# phychip_plugin_board.net
KiCad netlist of a schematic drawn in EAGLE
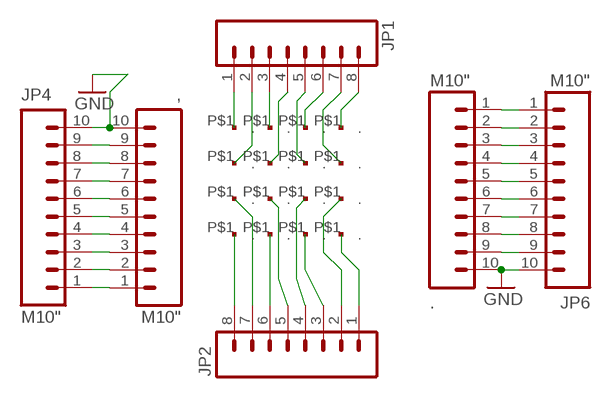
[diagram p0: schematic, sheet 1]

(export (version "E")
  (design (tool "Eeschema 10.0.6"))
  (components
    (comp (ref ",")
      (value "M10\"")
      (footprint "eagle-import:1X10")
      (libsource (lib "eagle-import") (part "M10{dblquote}"))
    )
    (comp (ref ".")
      (value "M10\"")
      (footprint "eagle-import:1X10")
      (libsource (lib "eagle-import") (part "M10{dblquote}"))
    )
    (comp (ref "JP1")
      (value "M08")
      (footprint "eagle-import:1X08")
      (libsource (lib "eagle-import") (part "M08"))
    )
    (comp (ref "JP2")
      (value "M08")
      (footprint "eagle-import:1X08")
      (libsource (lib "eagle-import") (part "M08"))
    )
    (comp (ref "JP4")
      (value "M10\"")
      (footprint "eagle-import:1X10")
      (libsource (lib "eagle-import") (part "M10{dblquote}"))
    )
    (comp (ref "JP6")
      (value "M10\"")
      (footprint "eagle-import:1X10")
      (libsource (lib "eagle-import") (part "M10{dblquote}"))
    )
    (comp (ref "U$1")
      (value "MEAPAD")
      (footprint "eagle-import:MEAPAD1MM")
      (libsource (lib "eagle-import") (part "MEAPAD"))
    )
    (comp (ref "U$2")
      (value "MEAPAD")
      (footprint "eagle-import:MEAPAD1MM")
      (libsource (lib "eagle-import") (part "MEAPAD"))
    )
    (comp (ref "U$3")
      (value "MEAPAD")
      (footprint "eagle-import:MEAPAD1MM")
      (libsource (lib "eagle-import") (part "MEAPAD"))
    )
    (comp (ref "U$4")
      (value "MEAPAD")
      (footprint "eagle-import:MEAPAD1MM")
      (libsource (lib "eagle-import") (part "MEAPAD"))
    )
    (comp (ref "U$5")
      (value "MEAPAD")
      (footprint "eagle-import:MEAPAD1MM")
      (libsource (lib "eagle-import") (part "MEAPAD"))
    )
    (comp (ref "U$6")
      (value "MEAPAD")
      (footprint "eagle-import:MEAPAD1MM")
      (libsource (lib "eagle-import") (part "MEAPAD"))
    )
    (comp (ref "U$7")
      (value "MEAPAD")
      (footprint "eagle-import:MEAPAD1MM")
      (libsource (lib "eagle-import") (part "MEAPAD"))
    )
    (comp (ref "U$8")
      (value "MEAPAD")
      (footprint "eagle-import:MEAPAD1MM")
      (libsource (lib "eagle-import") (part "MEAPAD"))
    )
    (comp (ref "U$9")
      (value "MEAPAD")
      (footprint "eagle-import:MEAPAD1MM")
      (libsource (lib "eagle-import") (part "MEAPAD"))
    )
    (comp (ref "U$10")
      (value "MEAPAD")
      (footprint "eagle-import:MEAPAD1MM")
      (libsource (lib "eagle-import") (part "MEAPAD"))
    )
    (comp (ref "U$11")
      (value "MEAPAD")
      (footprint "eagle-import:MEAPAD1MM")
      (libsource (lib "eagle-import") (part "MEAPAD"))
    )
    (comp (ref "U$12")
      (value "MEAPAD")
      (footprint "eagle-import:MEAPAD1MM")
      (libsource (lib "eagle-import") (part "MEAPAD"))
    )
    (comp (ref "U$13")
      (value "MEAPAD")
      (footprint "eagle-import:MEAPAD1MM")
      (libsource (lib "eagle-import") (part "MEAPAD"))
    )
    (comp (ref "U$14")
      (value "MEAPAD")
      (footprint "eagle-import:MEAPAD1MM")
      (libsource (lib "eagle-import") (part "MEAPAD"))
    )
    (comp (ref "U$15")
      (value "MEAPAD")
      (footprint "eagle-import:MEAPAD1MM")
      (libsource (lib "eagle-import") (part "MEAPAD"))
    )
    (comp (ref "U$16")
      (value "MEAPAD")
      (footprint "eagle-import:MEAPAD1MM")
      (libsource (lib "eagle-import") (part "MEAPAD"))
    )
  )
  (nets
    (net (code "1") (name "GND") (class "Default")
      (node (ref ",") (pin "10") (pinfunction "10_10") (pintype "passive"))
      (node (ref ".") (pin "10") (pinfunction "10_10") (pintype "passive"))
      (node (ref "JP4") (pin "10") (pinfunction "10_10") (pintype "passive"))
      (node (ref "JP6") (pin "10") (pinfunction "10_10") (pintype "passive"))
    )
    (net (code "2") (name "Net-(,-Pad1)") (class "Default")
      (node (ref ",") (pin "1") (pinfunction "1_1") (pintype "passive"))
      (node (ref "JP4") (pin "1") (pinfunction "1_1") (pintype "passive"))
    )
    (net (code "3") (name "Net-(,-Pad2)") (class "Default")
      (node (ref ",") (pin "2") (pinfunction "2_2") (pintype "passive"))
      (node (ref "JP4") (pin "2") (pinfunction "2_2") (pintype "passive"))
    )
    (net (code "4") (name "Net-(,-Pad3)") (class "Default")
      (node (ref ",") (pin "3") (pinfunction "3_3") (pintype "passive"))
      (node (ref "JP4") (pin "3") (pinfunction "3_3") (pintype "passive"))
    )
    (net (code "5") (name "Net-(,-Pad4)") (class "Default")
      (node (ref ",") (pin "4") (pinfunction "4_4") (pintype "passive"))
      (node (ref "JP4") (pin "4") (pinfunction "4_4") (pintype "passive"))
    )
    (net (code "6") (name "Net-(,-Pad5)") (class "Default")
      (node (ref ",") (pin "5") (pinfunction "5_5") (pintype "passive"))
      (node (ref "JP4") (pin "5") (pinfunction "5_5") (pintype "passive"))
    )
    (net (code "7") (name "Net-(,-Pad6)") (class "Default")
      (node (ref ",") (pin "6") (pinfunction "6_6") (pintype "passive"))
      (node (ref "JP4") (pin "6") (pinfunction "6_6") (pintype "passive"))
    )
    (net (code "8") (name "Net-(,-Pad7)") (class "Default")
      (node (ref ",") (pin "7") (pinfunction "7_7") (pintype "passive"))
      (node (ref "JP4") (pin "7") (pinfunction "7_7") (pintype "passive"))
    )
    (net (code "9") (name "Net-(,-Pad8)") (class "Default")
      (node (ref ",") (pin "8") (pinfunction "8_8") (pintype "passive"))
      (node (ref "JP4") (pin "8") (pinfunction "8_8") (pintype "passive"))
    )
    (net (code "10") (name "Net-(,-Pad9)") (class "Default")
      (node (ref ",") (pin "9") (pinfunction "9_9") (pintype "passive"))
      (node (ref "JP4") (pin "9") (pinfunction "9_9") (pintype "passive"))
    )
    (net (code "11") (name "Net-(.-Pad1)") (class "Default")
      (node (ref ".") (pin "1") (pinfunction "1_1") (pintype "passive"))
      (node (ref "JP6") (pin "1") (pinfunction "1_1") (pintype "passive"))
    )
    (net (code "12") (name "Net-(.-Pad2)") (class "Default")
      (node (ref ".") (pin "2") (pinfunction "2_2") (pintype "passive"))
      (node (ref "JP6") (pin "2") (pinfunction "2_2") (pintype "passive"))
    )
    (net (code "13") (name "Net-(.-Pad3)") (class "Default")
      (node (ref ".") (pin "3") (pinfunction "3_3") (pintype "passive"))
      (node (ref "JP6") (pin "3") (pinfunction "3_3") (pintype "passive"))
    )
    (net (code "14") (name "Net-(.-Pad4)") (class "Default")
      (node (ref ".") (pin "4") (pinfunction "4_4") (pintype "passive"))
      (node (ref "JP6") (pin "4") (pinfunction "4_4") (pintype "passive"))
    )
    (net (code "15") (name "Net-(.-Pad5)") (class "Default")
      (node (ref ".") (pin "5") (pinfunction "5_5") (pintype "passive"))
      (node (ref "JP6") (pin "5") (pinfunction "5_5") (pintype "passive"))
    )
    (net (code "16") (name "Net-(.-Pad6)") (class "Default")
      (node (ref ".") (pin "6") (pinfunction "6_6") (pintype "passive"))
      (node (ref "JP6") (pin "6") (pinfunction "6_6") (pintype "passive"))
    )
    (net (code "17") (name "Net-(.-Pad7)") (class "Default")
      (node (ref ".") (pin "7") (pinfunction "7_7") (pintype "passive"))
      (node (ref "JP6") (pin "7") (pinfunction "7_7") (pintype "passive"))
    )
    (net (code "18") (name "Net-(.-Pad8)") (class "Default")
      (node (ref ".") (pin "8") (pinfunction "8_8") (pintype "passive"))
      (node (ref "JP6") (pin "8") (pinfunction "8_8") (pintype "passive"))
    )
    (net (code "19") (name "Net-(.-Pad9)") (class "Default")
      (node (ref ".") (pin "9") (pinfunction "9_9") (pintype "passive"))
      (node (ref "JP6") (pin "9") (pinfunction "9_9") (pintype "passive"))
    )
    (net (code "20") (name "Net-(U$1-.)") (class "Default")
      (node (ref "JP1") (pin "1") (pinfunction "1_1") (pintype "passive"))
      (node (ref "U$1") (pin "P$1") (pinfunction "._P$1") (pintype "bidirectional"))
    )
    (net (code "21") (name "Net-(U$2-.)") (class "Default")
      (node (ref "JP1") (pin "3") (pinfunction "3_3") (pintype "passive"))
      (node (ref "U$2") (pin "P$1") (pinfunction "._P$1") (pintype "bidirectional"))
    )
    (net (code "22") (name "Net-(U$3-.)") (class "Default")
      (node (ref "JP1") (pin "6") (pinfunction "6_6") (pintype "passive"))
      (node (ref "U$3") (pin "P$1") (pinfunction "._P$1") (pintype "bidirectional"))
    )
    (net (code "23") (name "Net-(U$4-.)") (class "Default")
      (node (ref "JP1") (pin "8") (pinfunction "8_8") (pintype "passive"))
      (node (ref "U$4") (pin "P$1") (pinfunction "._P$1") (pintype "bidirectional"))
    )
    (net (code "24") (name "Net-(U$5-.)") (class "Default")
      (node (ref "JP1") (pin "2") (pinfunction "2_2") (pintype "passive"))
      (node (ref "U$5") (pin "P$1") (pinfunction "._P$1") (pintype "bidirectional"))
    )
    (net (code "25") (name "Net-(U$6-.)") (class "Default")
      (node (ref "JP1") (pin "4") (pinfunction "4_4") (pintype "passive"))
      (node (ref "U$6") (pin "P$1") (pinfunction "._P$1") (pintype "bidirectional"))
    )
    (net (code "26") (name "Net-(U$7-.)") (class "Default")
      (node (ref "JP1") (pin "5") (pinfunction "5_5") (pintype "passive"))
      (node (ref "U$7") (pin "P$1") (pinfunction "._P$1") (pintype "bidirectional"))
    )
    (net (code "27") (name "Net-(U$8-.)") (class "Default")
      (node (ref "JP1") (pin "7") (pinfunction "7_7") (pintype "passive"))
      (node (ref "U$8") (pin "P$1") (pinfunction "._P$1") (pintype "bidirectional"))
    )
    (net (code "28") (name "Net-(U$9-.)") (class "Default")
      (node (ref "JP2") (pin "7") (pinfunction "7_7") (pintype "passive"))
      (node (ref "U$9") (pin "P$1") (pinfunction "._P$1") (pintype "bidirectional"))
    )
    (net (code "29") (name "Net-(U$10-.)") (class "Default")
      (node (ref "JP2") (pin "5") (pinfunction "5_5") (pintype "passive"))
      (node (ref "U$10") (pin "P$1") (pinfunction "._P$1") (pintype "bidirectional"))
    )
    (net (code "30") (name "Net-(U$11-.)") (class "Default")
      (node (ref "JP2") (pin "4") (pinfunction "4_4") (pintype "passive"))
      (node (ref "U$11") (pin "P$1") (pinfunction "._P$1") (pintype "bidirectional"))
    )
    (net (code "31") (name "Net-(U$12-.)") (class "Default")
      (node (ref "JP2") (pin "2") (pinfunction "2_2") (pintype "passive"))
      (node (ref "U$12") (pin "P$1") (pinfunction "._P$1") (pintype "bidirectional"))
    )
    (net (code "32") (name "Net-(U$13-.)") (class "Default")
      (node (ref "JP2") (pin "8") (pinfunction "8_8") (pintype "passive"))
      (node (ref "U$13") (pin "P$1") (pinfunction "._P$1") (pintype "bidirectional"))
    )
    (net (code "33") (name "Net-(U$14-.)") (class "Default")
      (node (ref "JP2") (pin "6") (pinfunction "6_6") (pintype "passive"))
      (node (ref "U$14") (pin "P$1") (pinfunction "._P$1") (pintype "bidirectional"))
    )
    (net (code "34") (name "Net-(U$15-.)") (class "Default")
      (node (ref "JP2") (pin "3") (pinfunction "3_3") (pintype "passive"))
      (node (ref "U$15") (pin "P$1") (pinfunction "._P$1") (pintype "bidirectional"))
    )
    (net (code "35") (name "Net-(U$16-.)") (class "Default")
      (node (ref "JP2") (pin "1") (pinfunction "1_1") (pintype "passive"))
      (node (ref "U$16") (pin "P$1") (pinfunction "._P$1") (pintype "bidirectional"))
    )
  )
)
